# CAN.net
KiCad netlist of a schematic drawn in Altium Designer
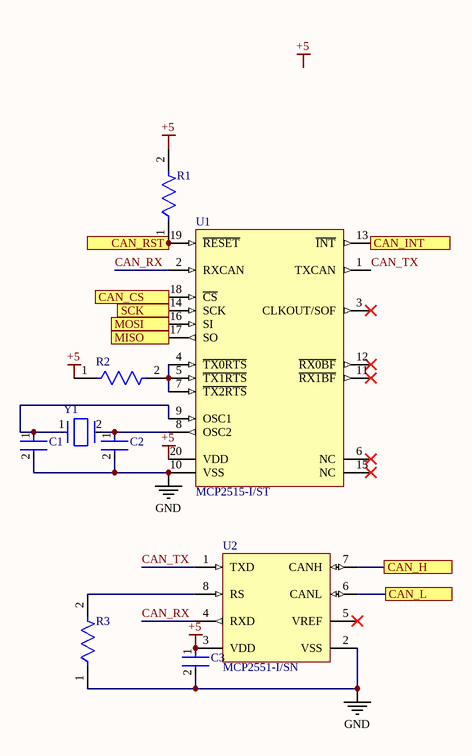
[diagram p0: CAN.SchDoc]

(export (version "E")
  (design (tool "Eeschema 10.0.6"))
  (components
    (comp (ref "C1")
      (value "C0603C220J5GACTU")
      (footprint "FP-C0603C-CF-MFG")
      (description "C0603 22 pF C0G 30ppm/°C 5.00% 50 V")
      (fields (field (name "TOLERANCE") "0.05"))
      (libsource (lib "Altium Content Vault") (part "b4654b650e69147ec39a6b967a45e02"))
    )
    (comp (ref "C2")
      (value "C0603C220J5GACTU")
      (footprint "FP-C0603C-CF-MFG")
      (description "C0603 22 pF C0G 30ppm/°C 5.00% 50 V")
      (fields (field (name "TOLERANCE") "0.05"))
      (libsource (lib "Altium Content Vault") (part "b4654b650e69147ec39a6b967a45e02"))
    )
    (comp (ref "C3")
      (value "GRM033R60J104KE19D")
      (footprint "FP-GRM033-0_03-MFG")
      (description "Chip Multilayer Ceramic Capacitors for General Purpose, 0201, 0.10uF, X5R, 15%, 10%, 6.3V")
      (fields (field (name "VOLTAGE") "6.3V") (field (name "TOLERANCE") "10%"))
      (libsource (lib "Altium Content Vault") (part "b4654b650e69147ec39a6b967a45e02"))
    )
    (comp (ref "R1")
      (value "ERJ-2RKF1003X")
      (footprint "FP-ERJ2RK-IPC_C")
      (description "RES SMD 100K OHM 1% 1/10W 0402")
      (fields (field (name "TOLERANCE") "1%"))
      (libsource (lib "Altium Content Vault") (part "1029c3af85768c4190bb7ad29bc67b5"))
    )
    (comp (ref "R2")
      (value "ERJ-2RKF1003X")
      (footprint "FP-ERJ2RK-IPC_C")
      (description "RES SMD 100K OHM 1% 1/10W 0402")
      (fields (field (name "TOLERANCE") "1%"))
      (libsource (lib "Altium Content Vault") (part "1029c3af85768c4190bb7ad29bc67b5"))
    )
    (comp (ref "R3")
      (value "ERJ-3GEYJ100V")
      (footprint "FP-ERJ3G-MFG")
      (description "Thick Film Resistors - SMD 0603 10ohms 5% AEC-Q200")
      (fields (field (name "TOLERANCE") "5%"))
      (libsource (lib "Altium Content Vault") (part "1029c3af85768c4190bb7ad29bc67b5"))
    )
    (comp (ref "U1")
      (value "MCP2515-I/ST")
      (footprint "TSSOP-ST20_N")
      (description "Stand-Alone CAN Controller With SPI Interface, 20-Pin TSSOP, Industrial Temperature")
      (libsource (lib "Altium Content Vault") (part "COM-CAN-MCP2515-20"))
    )
    (comp (ref "U2")
      (value "MCP2551-I/SN")
      (footprint "MCHP-SN8_V")
      (fields (field (name "MANUFACTURER") "Microchip"))
      (libsource (lib "Altium Content Vault") (part "MCHP-MCP2551-SN8"))
    )
    (comp (ref "Y1")
      (value "ABLS-16.000MHZ-K4T")
      (footprint "FP-ABLS-MFG")
      (description "16MHz ±30ppm Crystal 18pF 40 Ohms HC-49/US")
      (fields (field (name "TOLERANCE") "30ppm"))
      (libsource (lib "Altium Content Vault") (part "c23a69dc6c9e2f18f2079038eb95dd1"))
    )
  )
  (nets
    (net (code "1") (name "+5") (class "Default")
      (node (ref "C3") (pin "1") (pinfunction "1_1") (pintype "passive"))
      (node (ref "R1") (pin "2") (pinfunction "2_2") (pintype "passive"))
      (node (ref "R2") (pin "1") (pinfunction "1_1") (pintype "passive"))
      (node (ref "U1") (pin "20") (pinfunction "VDD_20") (pintype "power_in"))
      (node (ref "U2") (pin "3") (pinfunction "VDD_3") (pintype "power_in"))
    )
    (net (code "2") (name "/CAN_CS") (class "Default")
      (node (ref "U1") (pin "18") (pinfunction "~{CS}_18") (pintype "input"))
    )
    (net (code "3") (name "/CAN_H") (class "Default")
      (node (ref "U2") (pin "7") (pinfunction "CANH_7") (pintype "bidirectional"))
    )
    (net (code "4") (name "/CAN_INT") (class "Default")
      (node (ref "U1") (pin "13") (pinfunction "~{INT}_13") (pintype "output"))
    )
    (net (code "5") (name "/CAN_L") (class "Default")
      (node (ref "U2") (pin "6") (pinfunction "CANL_6") (pintype "bidirectional"))
    )
    (net (code "6") (name "/CAN_RST") (class "Default")
      (node (ref "R1") (pin "1") (pinfunction "1_1") (pintype "passive"))
      (node (ref "U1") (pin "19") (pinfunction "~{RESET}_19") (pintype "input"))
    )
    (net (code "7") (name "/CAN_RX") (class "Default")
      (node (ref "U1") (pin "2") (pinfunction "RXCAN_2") (pintype "input"))
      (node (ref "U2") (pin "4") (pinfunction "RXD_4") (pintype "output"))
    )
    (net (code "8") (name "/CAN_TX") (class "Default")
      (node (ref "U1") (pin "1") (pinfunction "TXCAN_1") (pintype "output"))
      (node (ref "U2") (pin "1") (pinfunction "TXD_1") (pintype "input"))
    )
    (net (code "9") (name "/MISO") (class "Default")
      (node (ref "U1") (pin "17") (pinfunction "SO_17") (pintype "output"))
    )
    (net (code "10") (name "/MOSI") (class "Default")
      (node (ref "U1") (pin "16") (pinfunction "SI_16") (pintype "input"))
    )
    (net (code "11") (name "/SCK") (class "Default")
      (node (ref "U1") (pin "14") (pinfunction "SCK_14") (pintype "input"))
    )
    (net (code "12") (name "GND") (class "Default")
      (node (ref "C1") (pin "2") (pinfunction "2_2") (pintype "passive"))
      (node (ref "C2") (pin "2") (pinfunction "2_2") (pintype "passive"))
      (node (ref "C3") (pin "2") (pinfunction "2_2") (pintype "passive"))
      (node (ref "R3") (pin "1") (pinfunction "1_1") (pintype "passive"))
      (node (ref "U1") (pin "10") (pinfunction "VSS_10") (pintype "power_in"))
      (node (ref "U2") (pin "2") (pinfunction "VSS_2") (pintype "power_in"))
    )
    (net (code "13") (name "Net-(U1-OSC1)") (class "Default")
      (node (ref "C1") (pin "1") (pinfunction "1_1") (pintype "passive"))
      (node (ref "U1") (pin "9") (pinfunction "OSC1_9") (pintype "input"))
      (node (ref "Y1") (pin "1") (pinfunction "1_1") (pintype "passive"))
    )
    (net (code "14") (name "Net-(U1-OSC2)") (class "Default")
      (node (ref "C2") (pin "1") (pinfunction "1_1") (pintype "passive"))
      (node (ref "U1") (pin "8") (pinfunction "OSC2_8") (pintype "output"))
      (node (ref "Y1") (pin "2") (pinfunction "2_2") (pintype "passive"))
    )
    (net (code "15") (name "Net-(U1-~{TX0RTS})") (class "Default")
      (node (ref "R2") (pin "2") (pinfunction "2_2") (pintype "passive"))
      (node (ref "U1") (pin "4") (pinfunction "~{TX0RTS}_4") (pintype "input"))
      (node (ref "U1") (pin "5") (pinfunction "~{TX1RTS}_5") (pintype "input"))
      (node (ref "U1") (pin "7") (pinfunction "~{TX2RTS}_7") (pintype "input"))
    )
    (net (code "16") (name "Net-(U2-RS)") (class "Default")
      (node (ref "R3") (pin "2") (pinfunction "2_2") (pintype "passive"))
      (node (ref "U2") (pin "8") (pinfunction "RS_8") (pintype "input"))
    )
    (net (code "17") (name "unconnected-(U1-CLKOUT{slash}SOF-Pad3)") (class "Default")
      (node (ref "U1") (pin "3") (pinfunction "CLKOUT/SOF_3") (pintype "output+no_connect"))
    )
    (net (code "18") (name "unconnected-(U1-NC-Pad6)") (class "Default")
      (node (ref "U1") (pin "6") (pinfunction "NC_6") (pintype "passive+no_connect"))
    )
    (net (code "19") (name "unconnected-(U1-NC-Pad15)") (class "Default")
      (node (ref "U1") (pin "15") (pinfunction "NC_15") (pintype "passive+no_connect"))
    )
    (net (code "20") (name "unconnected-(U1-~{RX0BF}-Pad12)") (class "Default")
      (node (ref "U1") (pin "12") (pinfunction "~{RX0BF}_12") (pintype "output+no_connect"))
    )
    (net (code "21") (name "unconnected-(U1-~{RX1BF}-Pad11)") (class "Default")
      (node (ref "U1") (pin "11") (pinfunction "~{RX1BF}_11") (pintype "output+no_connect"))
    )
    (net (code "22") (name "unconnected-(U2-VREF-Pad5)") (class "Default")
      (node (ref "U2") (pin "5") (pinfunction "VREF_5") (pintype "power_in+no_connect"))
    )
  )
)
